# connector-top-j3-0.net
KiCad netlist of a schematic drawn in Altium Designer
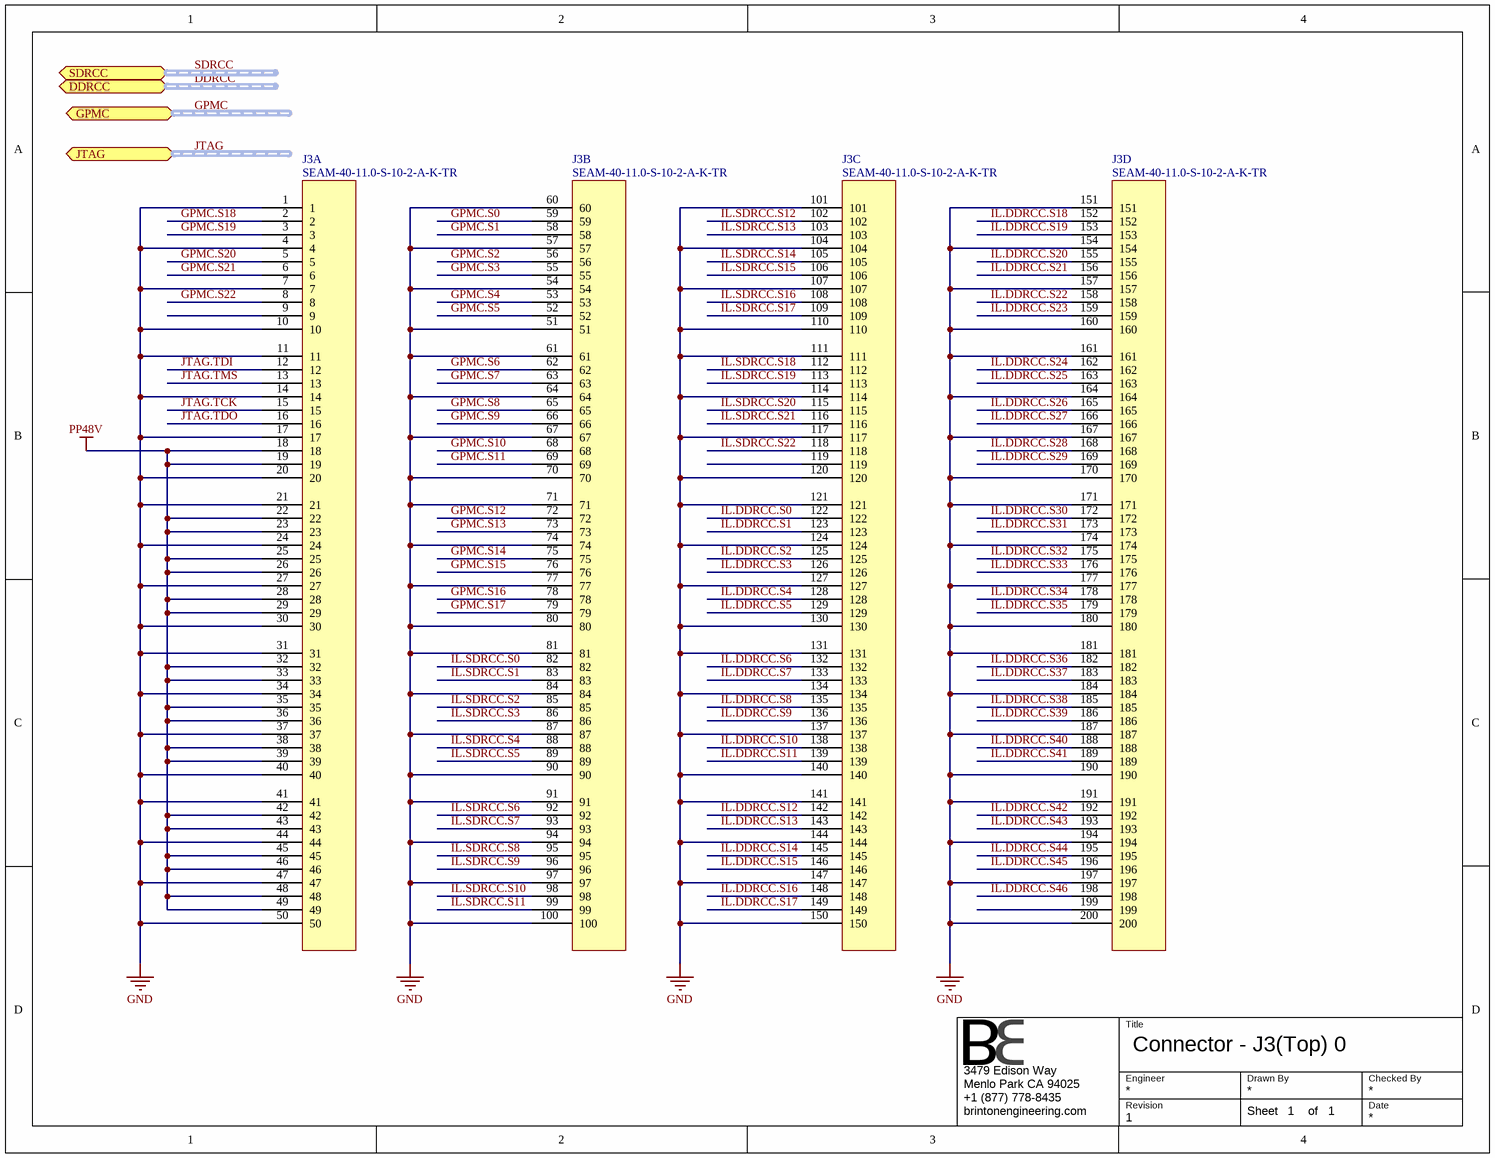
[diagram p0: connector-top-j3-0.SchDoc]

(export (version "E")
  (design (tool "Eeschema 10.0.6"))
  (components
    (comp (ref "J3")
      (value "SEAM-40-11.0-S-10-2-A-K-TR")
      (footprint "samtec:SEAM-40-11.0-S-10-2-A-K-TR")
      (description "Terminal Array Assembly, Surface Mount, 0.050\" Pitch, 400 Pins")
      (fields (field (name "MANUFACTURER") "Samtec"))
      (libsource (lib "samtec") (part "SEAM-40-11.0-S-10-2-A-K-TR"))
    )
  )
  (nets
    (net (code "5") (name "/GPMC.S0") (class "Default")
      (node (ref "J3") (pin "59") (pinfunction "59_59") (pintype "passive"))
    )
    (net (code "6") (name "/GPMC.S1") (class "Default")
      (node (ref "J3") (pin "58") (pinfunction "58_58") (pintype "passive"))
    )
    (net (code "7") (name "/GPMC.S2") (class "Default")
      (node (ref "J3") (pin "56") (pinfunction "56_56") (pintype "passive"))
    )
    (net (code "8") (name "/GPMC.S3") (class "Default")
      (node (ref "J3") (pin "55") (pinfunction "55_55") (pintype "passive"))
    )
    (net (code "9") (name "/GPMC.S4") (class "Default")
      (node (ref "J3") (pin "53") (pinfunction "53_53") (pintype "passive"))
    )
    (net (code "10") (name "/GPMC.S5") (class "Default")
      (node (ref "J3") (pin "52") (pinfunction "52_52") (pintype "passive"))
    )
    (net (code "11") (name "/GPMC.S6") (class "Default")
      (node (ref "J3") (pin "62") (pinfunction "62_62") (pintype "passive"))
    )
    (net (code "12") (name "/GPMC.S7") (class "Default")
      (node (ref "J3") (pin "63") (pinfunction "63_63") (pintype "passive"))
    )
    (net (code "13") (name "/GPMC.S8") (class "Default")
      (node (ref "J3") (pin "65") (pinfunction "65_65") (pintype "passive"))
    )
    (net (code "14") (name "/GPMC.S9") (class "Default")
      (node (ref "J3") (pin "66") (pinfunction "66_66") (pintype "passive"))
    )
    (net (code "15") (name "/GPMC.S10") (class "Default")
      (node (ref "J3") (pin "68") (pinfunction "68_68") (pintype "passive"))
    )
    (net (code "16") (name "/GPMC.S11") (class "Default")
      (node (ref "J3") (pin "69") (pinfunction "69_69") (pintype "passive"))
    )
    (net (code "17") (name "/GPMC.S12") (class "Default")
      (node (ref "J3") (pin "72") (pinfunction "72_72") (pintype "passive"))
    )
    (net (code "18") (name "/GPMC.S13") (class "Default")
      (node (ref "J3") (pin "73") (pinfunction "73_73") (pintype "passive"))
    )
    (net (code "19") (name "/GPMC.S14") (class "Default")
      (node (ref "J3") (pin "75") (pinfunction "75_75") (pintype "passive"))
    )
    (net (code "20") (name "/GPMC.S15") (class "Default")
      (node (ref "J3") (pin "76") (pinfunction "76_76") (pintype "passive"))
    )
    (net (code "21") (name "/GPMC.S16") (class "Default")
      (node (ref "J3") (pin "78") (pinfunction "78_78") (pintype "passive"))
    )
    (net (code "22") (name "/GPMC.S17") (class "Default")
      (node (ref "J3") (pin "79") (pinfunction "79_79") (pintype "passive"))
    )
    (net (code "23") (name "/GPMC.S18") (class "Default")
      (node (ref "J3") (pin "2") (pinfunction "2_2") (pintype "passive"))
    )
    (net (code "24") (name "/GPMC.S19") (class "Default")
      (node (ref "J3") (pin "3") (pinfunction "3_3") (pintype "passive"))
    )
    (net (code "25") (name "/GPMC.S20") (class "Default")
      (node (ref "J3") (pin "5") (pinfunction "5_5") (pintype "passive"))
    )
    (net (code "26") (name "/GPMC.S21") (class "Default")
      (node (ref "J3") (pin "6") (pinfunction "6_6") (pintype "passive"))
    )
    (net (code "27") (name "/GPMC.S22") (class "Default")
      (node (ref "J3") (pin "8") (pinfunction "8_8") (pintype "passive"))
    )
    (net (code "28") (name "/IL.DDRCC.S0") (class "Default")
      (node (ref "J3") (pin "122") (pinfunction "122_122") (pintype "passive"))
    )
    (net (code "29") (name "/IL.DDRCC.S1") (class "Default")
      (node (ref "J3") (pin "123") (pinfunction "123_123") (pintype "passive"))
    )
    (net (code "30") (name "/IL.DDRCC.S2") (class "Default")
      (node (ref "J3") (pin "125") (pinfunction "125_125") (pintype "passive"))
    )
    (net (code "31") (name "/IL.DDRCC.S3") (class "Default")
      (node (ref "J3") (pin "126") (pinfunction "126_126") (pintype "passive"))
    )
    (net (code "32") (name "/IL.DDRCC.S4") (class "Default")
      (node (ref "J3") (pin "128") (pinfunction "128_128") (pintype "passive"))
    )
    (net (code "33") (name "/IL.DDRCC.S5") (class "Default")
      (node (ref "J3") (pin "129") (pinfunction "129_129") (pintype "passive"))
    )
    (net (code "34") (name "/IL.DDRCC.S6") (class "Default")
      (node (ref "J3") (pin "132") (pinfunction "132_132") (pintype "passive"))
    )
    (net (code "35") (name "/IL.DDRCC.S7") (class "Default")
      (node (ref "J3") (pin "133") (pinfunction "133_133") (pintype "passive"))
    )
    (net (code "36") (name "/IL.DDRCC.S8") (class "Default")
      (node (ref "J3") (pin "135") (pinfunction "135_135") (pintype "passive"))
    )
    (net (code "37") (name "/IL.DDRCC.S9") (class "Default")
      (node (ref "J3") (pin "136") (pinfunction "136_136") (pintype "passive"))
    )
    (net (code "38") (name "/IL.DDRCC.S10") (class "Default")
      (node (ref "J3") (pin "138") (pinfunction "138_138") (pintype "passive"))
    )
    (net (code "39") (name "/IL.DDRCC.S11") (class "Default")
      (node (ref "J3") (pin "139") (pinfunction "139_139") (pintype "passive"))
    )
    (net (code "40") (name "/IL.DDRCC.S12") (class "Default")
      (node (ref "J3") (pin "142") (pinfunction "142_142") (pintype "passive"))
    )
    (net (code "41") (name "/IL.DDRCC.S13") (class "Default")
      (node (ref "J3") (pin "143") (pinfunction "143_143") (pintype "passive"))
    )
    (net (code "42") (name "/IL.DDRCC.S14") (class "Default")
      (node (ref "J3") (pin "145") (pinfunction "145_145") (pintype "passive"))
    )
    (net (code "43") (name "/IL.DDRCC.S15") (class "Default")
      (node (ref "J3") (pin "146") (pinfunction "146_146") (pintype "passive"))
    )
    (net (code "44") (name "/IL.DDRCC.S16") (class "Default")
      (node (ref "J3") (pin "148") (pinfunction "148_148") (pintype "passive"))
    )
    (net (code "45") (name "/IL.DDRCC.S17") (class "Default")
      (node (ref "J3") (pin "149") (pinfunction "149_149") (pintype "passive"))
    )
    (net (code "46") (name "/IL.DDRCC.S18") (class "Default")
      (node (ref "J3") (pin "152") (pinfunction "152_152") (pintype "passive"))
    )
    (net (code "47") (name "/IL.DDRCC.S19") (class "Default")
      (node (ref "J3") (pin "153") (pinfunction "153_153") (pintype "passive"))
    )
    (net (code "48") (name "/IL.DDRCC.S20") (class "Default")
      (node (ref "J3") (pin "155") (pinfunction "155_155") (pintype "passive"))
    )
    (net (code "49") (name "/IL.DDRCC.S21") (class "Default")
      (node (ref "J3") (pin "156") (pinfunction "156_156") (pintype "passive"))
    )
    (net (code "50") (name "/IL.DDRCC.S22") (class "Default")
      (node (ref "J3") (pin "158") (pinfunction "158_158") (pintype "passive"))
    )
    (net (code "51") (name "/IL.DDRCC.S23") (class "Default")
      (node (ref "J3") (pin "159") (pinfunction "159_159") (pintype "passive"))
    )
    (net (code "52") (name "/IL.DDRCC.S24") (class "Default")
      (node (ref "J3") (pin "162") (pinfunction "162_162") (pintype "passive"))
    )
    (net (code "53") (name "/IL.DDRCC.S25") (class "Default")
      (node (ref "J3") (pin "163") (pinfunction "163_163") (pintype "passive"))
    )
    (net (code "54") (name "/IL.DDRCC.S26") (class "Default")
      (node (ref "J3") (pin "165") (pinfunction "165_165") (pintype "passive"))
    )
    (net (code "55") (name "/IL.DDRCC.S27") (class "Default")
      (node (ref "J3") (pin "166") (pinfunction "166_166") (pintype "passive"))
    )
    (net (code "56") (name "/IL.DDRCC.S28") (class "Default")
      (node (ref "J3") (pin "168") (pinfunction "168_168") (pintype "passive"))
    )
    (net (code "57") (name "/IL.DDRCC.S29") (class "Default")
      (node (ref "J3") (pin "169") (pinfunction "169_169") (pintype "passive"))
    )
    (net (code "58") (name "/IL.DDRCC.S30") (class "Default")
      (node (ref "J3") (pin "172") (pinfunction "172_172") (pintype "passive"))
    )
    (net (code "59") (name "/IL.DDRCC.S31") (class "Default")
      (node (ref "J3") (pin "173") (pinfunction "173_173") (pintype "passive"))
    )
    (net (code "60") (name "/IL.DDRCC.S32") (class "Default")
      (node (ref "J3") (pin "175") (pinfunction "175_175") (pintype "passive"))
    )
    (net (code "61") (name "/IL.DDRCC.S33") (class "Default")
      (node (ref "J3") (pin "176") (pinfunction "176_176") (pintype "passive"))
    )
    (net (code "62") (name "/IL.DDRCC.S34") (class "Default")
      (node (ref "J3") (pin "178") (pinfunction "178_178") (pintype "passive"))
    )
    (net (code "63") (name "/IL.DDRCC.S35") (class "Default")
      (node (ref "J3") (pin "179") (pinfunction "179_179") (pintype "passive"))
    )
    (net (code "64") (name "/IL.DDRCC.S36") (class "Default")
      (node (ref "J3") (pin "182") (pinfunction "182_182") (pintype "passive"))
    )
    (net (code "65") (name "/IL.DDRCC.S37") (class "Default")
      (node (ref "J3") (pin "183") (pinfunction "183_183") (pintype "passive"))
    )
    (net (code "66") (name "/IL.DDRCC.S38") (class "Default")
      (node (ref "J3") (pin "185") (pinfunction "185_185") (pintype "passive"))
    )
    (net (code "67") (name "/IL.DDRCC.S39") (class "Default")
      (node (ref "J3") (pin "186") (pinfunction "186_186") (pintype "passive"))
    )
    (net (code "68") (name "/IL.DDRCC.S40") (class "Default")
      (node (ref "J3") (pin "188") (pinfunction "188_188") (pintype "passive"))
    )
    (net (code "69") (name "/IL.DDRCC.S41") (class "Default")
      (node (ref "J3") (pin "189") (pinfunction "189_189") (pintype "passive"))
    )
    (net (code "70") (name "/IL.DDRCC.S42") (class "Default")
      (node (ref "J3") (pin "192") (pinfunction "192_192") (pintype "passive"))
    )
    (net (code "71") (name "/IL.DDRCC.S43") (class "Default")
      (node (ref "J3") (pin "193") (pinfunction "193_193") (pintype "passive"))
    )
    (net (code "72") (name "/IL.DDRCC.S44") (class "Default")
      (node (ref "J3") (pin "195") (pinfunction "195_195") (pintype "passive"))
    )
    (net (code "73") (name "/IL.DDRCC.S45") (class "Default")
      (node (ref "J3") (pin "196") (pinfunction "196_196") (pintype "passive"))
    )
    (net (code "74") (name "/IL.DDRCC.S46") (class "Default")
      (node (ref "J3") (pin "198") (pinfunction "198_198") (pintype "passive"))
    )
    (net (code "75") (name "/IL.SDRCC.S0") (class "Default")
      (node (ref "J3") (pin "82") (pinfunction "82_82") (pintype "passive"))
    )
    (net (code "76") (name "/IL.SDRCC.S1") (class "Default")
      (node (ref "J3") (pin "83") (pinfunction "83_83") (pintype "passive"))
    )
    (net (code "77") (name "/IL.SDRCC.S2") (class "Default")
      (node (ref "J3") (pin "85") (pinfunction "85_85") (pintype "passive"))
    )
    (net (code "78") (name "/IL.SDRCC.S3") (class "Default")
      (node (ref "J3") (pin "86") (pinfunction "86_86") (pintype "passive"))
    )
    (net (code "79") (name "/IL.SDRCC.S4") (class "Default")
      (node (ref "J3") (pin "88") (pinfunction "88_88") (pintype "passive"))
    )
    (net (code "80") (name "/IL.SDRCC.S5") (class "Default")
      (node (ref "J3") (pin "89") (pinfunction "89_89") (pintype "passive"))
    )
    (net (code "81") (name "/IL.SDRCC.S6") (class "Default")
      (node (ref "J3") (pin "92") (pinfunction "92_92") (pintype "passive"))
    )
    (net (code "82") (name "/IL.SDRCC.S7") (class "Default")
      (node (ref "J3") (pin "93") (pinfunction "93_93") (pintype "passive"))
    )
    (net (code "83") (name "/IL.SDRCC.S8") (class "Default")
      (node (ref "J3") (pin "95") (pinfunction "95_95") (pintype "passive"))
    )
    (net (code "84") (name "/IL.SDRCC.S9") (class "Default")
      (node (ref "J3") (pin "96") (pinfunction "96_96") (pintype "passive"))
    )
    (net (code "85") (name "/IL.SDRCC.S10") (class "Default")
      (node (ref "J3") (pin "98") (pinfunction "98_98") (pintype "passive"))
    )
    (net (code "86") (name "/IL.SDRCC.S11") (class "Default")
      (node (ref "J3") (pin "99") (pinfunction "99_99") (pintype "passive"))
    )
    (net (code "87") (name "/IL.SDRCC.S12") (class "Default")
      (node (ref "J3") (pin "102") (pinfunction "102_102") (pintype "passive"))
    )
    (net (code "88") (name "/IL.SDRCC.S13") (class "Default")
      (node (ref "J3") (pin "103") (pinfunction "103_103") (pintype "passive"))
    )
    (net (code "89") (name "/IL.SDRCC.S14") (class "Default")
      (node (ref "J3") (pin "105") (pinfunction "105_105") (pintype "passive"))
    )
    (net (code "90") (name "/IL.SDRCC.S15") (class "Default")
      (node (ref "J3") (pin "106") (pinfunction "106_106") (pintype "passive"))
    )
    (net (code "91") (name "/IL.SDRCC.S16") (class "Default")
      (node (ref "J3") (pin "108") (pinfunction "108_108") (pintype "passive"))
    )
    (net (code "92") (name "/IL.SDRCC.S17") (class "Default")
      (node (ref "J3") (pin "109") (pinfunction "109_109") (pintype "passive"))
    )
    (net (code "93") (name "/IL.SDRCC.S18") (class "Default")
      (node (ref "J3") (pin "112") (pinfunction "112_112") (pintype "passive"))
    )
    (net (code "94") (name "/IL.SDRCC.S19") (class "Default")
      (node (ref "J3") (pin "113") (pinfunction "113_113") (pintype "passive"))
    )
    (net (code "95") (name "/IL.SDRCC.S20") (class "Default")
      (node (ref "J3") (pin "115") (pinfunction "115_115") (pintype "passive"))
    )
    (net (code "96") (name "/IL.SDRCC.S21") (class "Default")
      (node (ref "J3") (pin "116") (pinfunction "116_116") (pintype "passive"))
    )
    (net (code "97") (name "/IL.SDRCC.S22") (class "Default")
      (node (ref "J3") (pin "118") (pinfunction "118_118") (pintype "passive"))
    )
    (net (code "98") (name "/JTAG.TCK") (class "Default")
      (node (ref "J3") (pin "15") (pinfunction "15_15") (pintype "passive"))
    )
    (net (code "99") (name "/JTAG.TDI") (class "Default")
      (node (ref "J3") (pin "12") (pinfunction "12_12") (pintype "passive"))
    )
    (net (code "100") (name "/JTAG.TDO") (class "Default")
      (node (ref "J3") (pin "16") (pinfunction "16_16") (pintype "passive"))
    )
    (net (code "101") (name "/JTAG.TMS") (class "Default")
      (node (ref "J3") (pin "13") (pinfunction "13_13") (pintype "passive"))
    )
    (net (code "106") (name "GND") (class "Default")
      (node (ref "J3") (pin "1") (pinfunction "1_1") (pintype "passive"))
      (node (ref "J3") (pin "10") (pinfunction "10_10") (pintype "passive"))
      (node (ref "J3") (pin "100") (pinfunction "100_100") (pintype "passive"))
      (node (ref "J3") (pin "101") (pinfunction "101_101") (pintype "passive"))
      (node (ref "J3") (pin "104") (pinfunction "104_104") (pintype "passive"))
      (node (ref "J3") (pin "107") (pinfunction "107_107") (pintype "passive"))
      (node (ref "J3") (pin "11") (pinfunction "11_11") (pintype "passive"))
      (node (ref "J3") (pin "110") (pinfunction "110_110") (pintype "passive"))
      (node (ref "J3") (pin "111") (pinfunction "111_111") (pintype "passive"))
      (node (ref "J3") (pin "114") (pinfunction "114_114") (pintype "passive"))
      (node (ref "J3") (pin "117") (pinfunction "117_117") (pintype "passive"))
      (node (ref "J3") (pin "120") (pinfunction "120_120") (pintype "passive"))
      (node (ref "J3") (pin "121") (pinfunction "121_121") (pintype "passive"))
      (node (ref "J3") (pin "124") (pinfunction "124_124") (pintype "passive"))
      (node (ref "J3") (pin "127") (pinfunction "127_127") (pintype "passive"))
      (node (ref "J3") (pin "130") (pinfunction "130_130") (pintype "passive"))
      (node (ref "J3") (pin "131") (pinfunction "131_131") (pintype "passive"))
      (node (ref "J3") (pin "134") (pinfunction "134_134") (pintype "passive"))
      (node (ref "J3") (pin "137") (pinfunction "137_137") (pintype "passive"))
      (node (ref "J3") (pin "14") (pinfunction "14_14") (pintype "passive"))
      (node (ref "J3") (pin "140") (pinfunction "140_140") (pintype "passive"))
      (node (ref "J3") (pin "141") (pinfunction "141_141") (pintype "passive"))
      (node (ref "J3") (pin "144") (pinfunction "144_144") (pintype "passive"))
      (node (ref "J3") (pin "147") (pinfunction "147_147") (pintype "passive"))
      (node (ref "J3") (pin "150") (pinfunction "150_150") (pintype "passive"))
      (node (ref "J3") (pin "151") (pinfunction "151_151") (pintype "passive"))
      (node (ref "J3") (pin "154") (pinfunction "154_154") (pintype "passive"))
      (node (ref "J3") (pin "157") (pinfunction "157_157") (pintype "passive"))
      (node (ref "J3") (pin "160") (pinfunction "160_160") (pintype "passive"))
      (node (ref "J3") (pin "161") (pinfunction "161_161") (pintype "passive"))
      (node (ref "J3") (pin "164") (pinfunction "164_164") (pintype "passive"))
      (node (ref "J3") (pin "167") (pinfunction "167_167") (pintype "passive"))
      (node (ref "J3") (pin "17") (pinfunction "17_17") (pintype "passive"))
      (node (ref "J3") (pin "170") (pinfunction "170_170") (pintype "passive"))
      (node (ref "J3") (pin "171") (pinfunction "171_171") (pintype "passive"))
      (node (ref "J3") (pin "174") (pinfunction "174_174") (pintype "passive"))
      (node (ref "J3") (pin "177") (pinfunction "177_177") (pintype "passive"))
      (node (ref "J3") (pin "180") (pinfunction "180_180") (pintype "passive"))
      (node (ref "J3") (pin "181") (pinfunction "181_181") (pintype "passive"))
      (node (ref "J3") (pin "184") (pinfunction "184_184") (pintype "passive"))
      (node (ref "J3") (pin "187") (pinfunction "187_187") (pintype "passive"))
      (node (ref "J3") (pin "190") (pinfunction "190_190") (pintype "passive"))
      (node (ref "J3") (pin "191") (pinfunction "191_191") (pintype "passive"))
      (node (ref "J3") (pin "194") (pinfunction "194_194") (pintype "passive"))
      (node (ref "J3") (pin "197") (pinfunction "197_197") (pintype "passive"))
      (node (ref "J3") (pin "20") (pinfunction "20_20") (pintype "passive"))
      (node (ref "J3") (pin "200") (pinfunction "200_200") (pintype "passive"))
      (node (ref "J3") (pin "21") (pinfunction "21_21") (pintype "passive"))
      (node (ref "J3") (pin "24") (pinfunction "24_24") (pintype "passive"))
      (node (ref "J3") (pin "27") (pinfunction "27_27") (pintype "passive"))
      (node (ref "J3") (pin "30") (pinfunction "30_30") (pintype "passive"))
      (node (ref "J3") (pin "31") (pinfunction "31_31") (pintype "passive"))
      (node (ref "J3") (pin "34") (pinfunction "34_34") (pintype "passive"))
      (node (ref "J3") (pin "37") (pinfunction "37_37") (pintype "passive"))
      (node (ref "J3") (pin "4") (pinfunction "4_4") (pintype "passive"))
      (node (ref "J3") (pin "40") (pinfunction "40_40") (pintype "passive"))
      (node (ref "J3") (pin "41") (pinfunction "41_41") (pintype "passive"))
      (node (ref "J3") (pin "44") (pinfunction "44_44") (pintype "passive"))
      (node (ref "J3") (pin "47") (pinfunction "47_47") (pintype "passive"))
      (node (ref "J3") (pin "50") (pinfunction "50_50") (pintype "passive"))
      (node (ref "J3") (pin "51") (pinfunction "51_51") (pintype "passive"))
      (node (ref "J3") (pin "54") (pinfunction "54_54") (pintype "passive"))
      (node (ref "J3") (pin "57") (pinfunction "57_57") (pintype "passive"))
      (node (ref "J3") (pin "60") (pinfunction "60_60") (pintype "passive"))
      (node (ref "J3") (pin "61") (pinfunction "61_61") (pintype "passive"))
      (node (ref "J3") (pin "64") (pinfunction "64_64") (pintype "passive"))
      (node (ref "J3") (pin "67") (pinfunction "67_67") (pintype "passive"))
      (node (ref "J3") (pin "7") (pinfunction "7_7") (pintype "passive"))
      (node (ref "J3") (pin "70") (pinfunction "70_70") (pintype "passive"))
      (node (ref "J3") (pin "71") (pinfunction "71_71") (pintype "passive"))
      (node (ref "J3") (pin "74") (pinfunction "74_74") (pintype "passive"))
      (node (ref "J3") (pin "77") (pinfunction "77_77") (pintype "passive"))
      (node (ref "J3") (pin "80") (pinfunction "80_80") (pintype "passive"))
      (node (ref "J3") (pin "81") (pinfunction "81_81") (pintype "passive"))
      (node (ref "J3") (pin "84") (pinfunction "84_84") (pintype "passive"))
      (node (ref "J3") (pin "87") (pinfunction "87_87") (pintype "passive"))
      (node (ref "J3") (pin "90") (pinfunction "90_90") (pintype "passive"))
      (node (ref "J3") (pin "91") (pinfunction "91_91") (pintype "passive"))
      (node (ref "J3") (pin "94") (pinfunction "94_94") (pintype "passive"))
      (node (ref "J3") (pin "97") (pinfunction "97_97") (pintype "passive"))
    )
    (net (code "107") (name "PP48V") (class "Default")
      (node (ref "J3") (pin "18") (pinfunction "18_18") (pintype "passive"))
      (node (ref "J3") (pin "19") (pinfunction "19_19") (pintype "passive"))
      (node (ref "J3") (pin "22") (pinfunction "22_22") (pintype "passive"))
      (node (ref "J3") (pin "23") (pinfunction "23_23") (pintype "passive"))
      (node (ref "J3") (pin "25") (pinfunction "25_25") (pintype "passive"))
      (node (ref "J3") (pin "26") (pinfunction "26_26") (pintype "passive"))
      (node (ref "J3") (pin "28") (pinfunction "28_28") (pintype "passive"))
      (node (ref "J3") (pin "29") (pinfunction "29_29") (pintype "passive"))
      (node (ref "J3") (pin "32") (pinfunction "32_32") (pintype "passive"))
      (node (ref "J3") (pin "33") (pinfunction "33_33") (pintype "passive"))
      (node (ref "J3") (pin "35") (pinfunction "35_35") (pintype "passive"))
      (node (ref "J3") (pin "36") (pinfunction "36_36") (pintype "passive"))
      (node (ref "J3") (pin "38") (pinfunction "38_38") (pintype "passive"))
      (node (ref "J3") (pin "39") (pinfunction "39_39") (pintype "passive"))
      (node (ref "J3") (pin "42") (pinfunction "42_42") (pintype "passive"))
      (node (ref "J3") (pin "43") (pinfunction "43_43") (pintype "passive"))
      (node (ref "J3") (pin "45") (pinfunction "45_45") (pintype "passive"))
      (node (ref "J3") (pin "46") (pinfunction "46_46") (pintype "passive"))
      (node (ref "J3") (pin "48") (pinfunction "48_48") (pintype "passive"))
      (node (ref "J3") (pin "49") (pinfunction "49_49") (pintype "passive"))
    )
    (net (code "108") (name "unconnected-(J3-Pad9)") (class "Default")
      (node (ref "J3") (pin "9") (pinfunction "9_9") (pintype "passive"))
    )
    (net (code "109") (name "unconnected-(J3-Pad119)") (class "Default")
      (node (ref "J3") (pin "119") (pinfunction "119_119") (pintype "passive"))
    )
    (net (code "110") (name "unconnected-(J3-Pad199)") (class "Default")
      (node (ref "J3") (pin "199") (pinfunction "199_199") (pintype "passive"))
    )
  )
)
